# Bank_A-B-C-D.net
KiCad netlist of a schematic drawn in Altium Designer
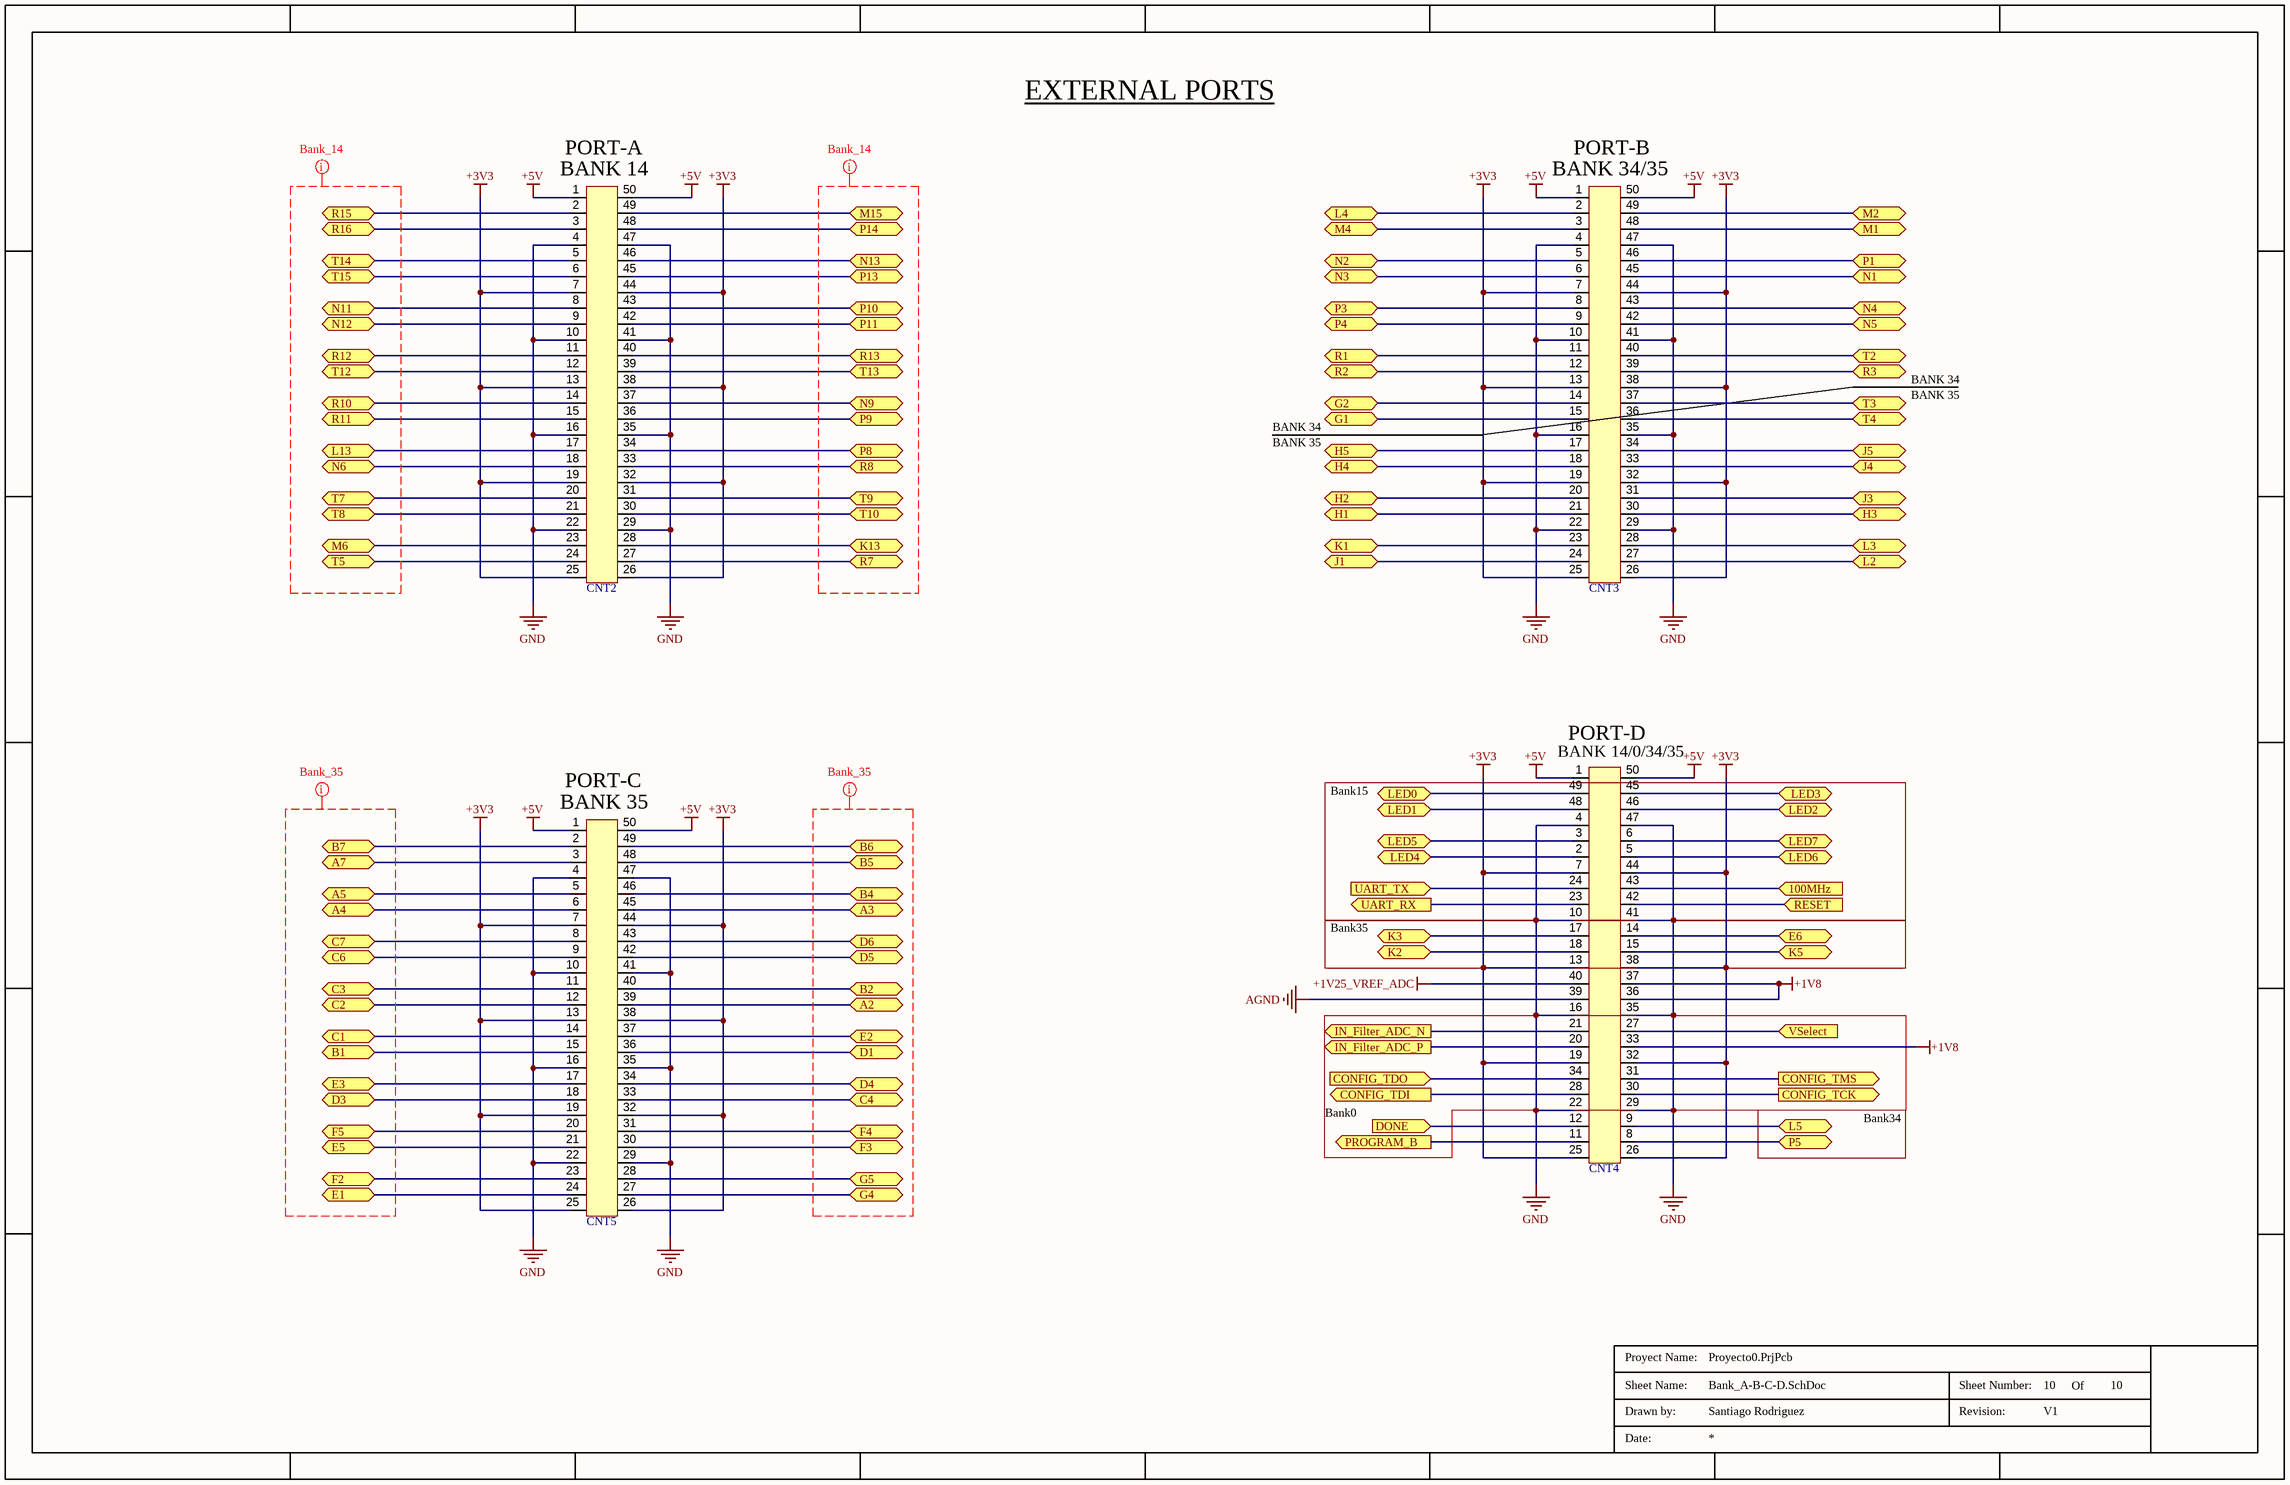
[diagram p0: Bank_A-B-C-D.SchDoc]

(export (version "E")
  (design (tool "Eeschema 10.0.6"))
  (components
    (comp (ref "CNT2")
      (value "528850574")
      (footprint "528850574")
      (description "CONN RCPT 50POS SMD GOLD")
      (fields (field (name "MANUFACTURER") "Molex") (field (name "PARTNUMBER") "0528850574"))
      (libsource (lib "Connectors") (part "528850574"))
    )
    (comp (ref "CNT3")
      (value "528850574")
      (footprint "528850574")
      (description "CONN RCPT 50POS SMD GOLD")
      (fields (field (name "MANUFACTURER") "Molex") (field (name "PARTNUMBER") "0528850574"))
      (libsource (lib "Connectors") (part "528850574"))
    )
    (comp (ref "CNT4")
      (value "528850574")
      (footprint "528850574")
      (description "CONN RCPT 50POS SMD GOLD")
      (fields (field (name "MANUFACTURER") "Molex") (field (name "PARTNUMBER") "0528850574"))
      (libsource (lib "") (part "528850574_1"))
    )
    (comp (ref "CNT5")
      (value "528850574")
      (footprint "528850574")
      (description "CONN RCPT 50POS SMD GOLD")
      (fields (field (name "MANUFACTURER") "Molex") (field (name "PARTNUMBER") "0528850574"))
      (libsource (lib "Connectors") (part "528850574"))
    )
  )
  (nets
    (net (code "1") (name "+1V8") (class "Default")
      (node (ref "CNT4") (pin "33") (pinfunction "33_33") (pintype "passive"))
      (node (ref "CNT4") (pin "36") (pinfunction "36_36") (pintype "passive"))
      (node (ref "CNT4") (pin "37") (pinfunction "37_37") (pintype "passive"))
    )
    (net (code "2") (name "+1V25_VREF_ADC") (class "Default")
      (node (ref "CNT4") (pin "40") (pinfunction "40_40") (pintype "passive"))
    )
    (net (code "3") (name "+3V3") (class "Default")
      (node (ref "CNT2") (pin "13") (pinfunction "13_13") (pintype "passive"))
      (node (ref "CNT2") (pin "19") (pinfunction "19_19") (pintype "passive"))
      (node (ref "CNT2") (pin "25") (pinfunction "25_25") (pintype "passive"))
      (node (ref "CNT2") (pin "26") (pinfunction "26_26") (pintype "passive"))
      (node (ref "CNT2") (pin "32") (pinfunction "32_32") (pintype "passive"))
      (node (ref "CNT2") (pin "38") (pinfunction "38_38") (pintype "passive"))
      (node (ref "CNT2") (pin "44") (pinfunction "44_44") (pintype "passive"))
      (node (ref "CNT2") (pin "7") (pinfunction "7_7") (pintype "passive"))
      (node (ref "CNT3") (pin "13") (pinfunction "13_13") (pintype "passive"))
      (node (ref "CNT3") (pin "19") (pinfunction "19_19") (pintype "passive"))
      (node (ref "CNT3") (pin "25") (pinfunction "25_25") (pintype "passive"))
      (node (ref "CNT3") (pin "26") (pinfunction "26_26") (pintype "passive"))
      (node (ref "CNT3") (pin "32") (pinfunction "32_32") (pintype "passive"))
      (node (ref "CNT3") (pin "38") (pinfunction "38_38") (pintype "passive"))
      (node (ref "CNT3") (pin "44") (pinfunction "44_44") (pintype "passive"))
      (node (ref "CNT3") (pin "7") (pinfunction "7_7") (pintype "passive"))
      (node (ref "CNT4") (pin "13") (pinfunction "13_13") (pintype "passive"))
      (node (ref "CNT4") (pin "19") (pinfunction "19_19") (pintype "passive"))
      (node (ref "CNT4") (pin "25") (pinfunction "25_25") (pintype "passive"))
      (node (ref "CNT4") (pin "26") (pinfunction "26_26") (pintype "passive"))
      (node (ref "CNT4") (pin "32") (pinfunction "32_32") (pintype "passive"))
      (node (ref "CNT4") (pin "38") (pinfunction "38_38") (pintype "passive"))
      (node (ref "CNT4") (pin "44") (pinfunction "44_44") (pintype "passive"))
      (node (ref "CNT4") (pin "7") (pinfunction "7_7") (pintype "passive"))
      (node (ref "CNT5") (pin "13") (pinfunction "13_13") (pintype "passive"))
      (node (ref "CNT5") (pin "19") (pinfunction "19_19") (pintype "passive"))
      (node (ref "CNT5") (pin "25") (pinfunction "25_25") (pintype "passive"))
      (node (ref "CNT5") (pin "26") (pinfunction "26_26") (pintype "passive"))
      (node (ref "CNT5") (pin "32") (pinfunction "32_32") (pintype "passive"))
      (node (ref "CNT5") (pin "38") (pinfunction "38_38") (pintype "passive"))
      (node (ref "CNT5") (pin "44") (pinfunction "44_44") (pintype "passive"))
      (node (ref "CNT5") (pin "7") (pinfunction "7_7") (pintype "passive"))
    )
    (net (code "4") (name "+5V") (class "Default")
      (node (ref "CNT2") (pin "1") (pintype "passive"))
      (node (ref "CNT2") (pin "50") (pinfunction "50_50") (pintype "passive"))
      (node (ref "CNT3") (pin "1") (pintype "passive"))
      (node (ref "CNT3") (pin "50") (pinfunction "50_50") (pintype "passive"))
      (node (ref "CNT4") (pin "1") (pintype "passive"))
      (node (ref "CNT4") (pin "50") (pinfunction "50_50") (pintype "passive"))
      (node (ref "CNT5") (pin "1") (pintype "passive"))
      (node (ref "CNT5") (pin "50") (pinfunction "50_50") (pintype "passive"))
    )
    (net (code "5") (name "/100MHz") (class "Default")
      (node (ref "CNT4") (pin "43") (pinfunction "43_43") (pintype "passive"))
    )
    (net (code "6") (name "/A2") (class "Default")
      (node (ref "CNT5") (pin "39") (pinfunction "39_39") (pintype "passive"))
    )
    (net (code "7") (name "/A3") (class "Default")
      (node (ref "CNT5") (pin "45") (pinfunction "45_45") (pintype "passive"))
    )
    (net (code "8") (name "/A4") (class "Default")
      (node (ref "CNT5") (pin "6") (pinfunction "6_6") (pintype "passive"))
    )
    (net (code "9") (name "/A5") (class "Default")
      (node (ref "CNT5") (pin "5") (pinfunction "5_5") (pintype "passive"))
    )
    (net (code "10") (name "/A7") (class "Default") (node (ref "CNT5") (pin "3") (pintype "passive")))
    (net (code "11") (name "/B1") (class "Default")
      (node (ref "CNT5") (pin "15") (pinfunction "15_15") (pintype "passive"))
    )
    (net (code "12") (name "/B2") (class "Default")
      (node (ref "CNT5") (pin "40") (pinfunction "40_40") (pintype "passive"))
    )
    (net (code "13") (name "/B4") (class "Default")
      (node (ref "CNT5") (pin "46") (pinfunction "46_46") (pintype "passive"))
    )
    (net (code "14") (name "/B5") (class "Default")
      (node (ref "CNT5") (pin "48") (pinfunction "48_48") (pintype "passive"))
    )
    (net (code "15") (name "/B6") (class "Default")
      (node (ref "CNT5") (pin "49") (pinfunction "49_49") (pintype "passive"))
    )
    (net (code "16") (name "/B7") (class "Default") (node (ref "CNT5") (pin "2") (pintype "passive")))
    (net (code "17") (name "/C1") (class "Default")
      (node (ref "CNT5") (pin "14") (pinfunction "14_14") (pintype "passive"))
    )
    (net (code "18") (name "/C2") (class "Default")
      (node (ref "CNT5") (pin "12") (pinfunction "12_12") (pintype "passive"))
    )
    (net (code "19") (name "/C3") (class "Default")
      (node (ref "CNT5") (pin "11") (pinfunction "11_11") (pintype "passive"))
    )
    (net (code "20") (name "/C4") (class "Default")
      (node (ref "CNT5") (pin "33") (pinfunction "33_33") (pintype "passive"))
    )
    (net (code "21") (name "/C6") (class "Default")
      (node (ref "CNT5") (pin "9") (pinfunction "9_9") (pintype "passive"))
    )
    (net (code "22") (name "/C7") (class "Default")
      (node (ref "CNT5") (pin "8") (pinfunction "8_8") (pintype "passive"))
    )
    (net (code "23") (name "/CONFIG_TCK") (class "Default")
      (node (ref "CNT4") (pin "30") (pinfunction "30_30") (pintype "passive"))
    )
    (net (code "24") (name "/CONFIG_TDI") (class "Default")
      (node (ref "CNT4") (pin "28") (pinfunction "28_28") (pintype "passive"))
    )
    (net (code "25") (name "/CONFIG_TDO") (class "Default")
      (node (ref "CNT4") (pin "34") (pinfunction "34_34") (pintype "passive"))
    )
    (net (code "26") (name "/CONFIG_TMS") (class "Default")
      (node (ref "CNT4") (pin "31") (pinfunction "31_31") (pintype "passive"))
    )
    (net (code "27") (name "/D1") (class "Default")
      (node (ref "CNT5") (pin "36") (pinfunction "36_36") (pintype "passive"))
    )
    (net (code "28") (name "/D3") (class "Default")
      (node (ref "CNT5") (pin "18") (pinfunction "18_18") (pintype "passive"))
    )
    (net (code "29") (name "/D4") (class "Default")
      (node (ref "CNT5") (pin "34") (pinfunction "34_34") (pintype "passive"))
    )
    (net (code "30") (name "/D5") (class "Default")
      (node (ref "CNT5") (pin "42") (pinfunction "42_42") (pintype "passive"))
    )
    (net (code "31") (name "/D6") (class "Default")
      (node (ref "CNT5") (pin "43") (pinfunction "43_43") (pintype "passive"))
    )
    (net (code "32") (name "/DONE") (class "Default")
      (node (ref "CNT4") (pin "12") (pinfunction "12_12") (pintype "passive"))
    )
    (net (code "33") (name "/E1") (class "Default")
      (node (ref "CNT5") (pin "24") (pinfunction "24_24") (pintype "passive"))
    )
    (net (code "34") (name "/E2") (class "Default")
      (node (ref "CNT5") (pin "37") (pinfunction "37_37") (pintype "passive"))
    )
    (net (code "35") (name "/E3") (class "Default")
      (node (ref "CNT5") (pin "17") (pinfunction "17_17") (pintype "passive"))
    )
    (net (code "36") (name "/E5") (class "Default")
      (node (ref "CNT5") (pin "21") (pinfunction "21_21") (pintype "passive"))
    )
    (net (code "37") (name "/E6") (class "Default")
      (node (ref "CNT4") (pin "14") (pinfunction "14_14") (pintype "passive"))
    )
    (net (code "38") (name "/F2") (class "Default")
      (node (ref "CNT5") (pin "23") (pinfunction "23_23") (pintype "passive"))
    )
    (net (code "39") (name "/F3") (class "Default")
      (node (ref "CNT5") (pin "30") (pinfunction "30_30") (pintype "passive"))
    )
    (net (code "40") (name "/F4") (class "Default")
      (node (ref "CNT5") (pin "31") (pinfunction "31_31") (pintype "passive"))
    )
    (net (code "41") (name "/F5") (class "Default")
      (node (ref "CNT5") (pin "20") (pinfunction "20_20") (pintype "passive"))
    )
    (net (code "42") (name "/G1") (class "Default")
      (node (ref "CNT3") (pin "15") (pinfunction "15_15") (pintype "passive"))
    )
    (net (code "43") (name "/G2") (class "Default")
      (node (ref "CNT3") (pin "14") (pinfunction "14_14") (pintype "passive"))
    )
    (net (code "44") (name "/G4") (class "Default")
      (node (ref "CNT5") (pin "27") (pinfunction "27_27") (pintype "passive"))
    )
    (net (code "45") (name "/G5") (class "Default")
      (node (ref "CNT5") (pin "28") (pinfunction "28_28") (pintype "passive"))
    )
    (net (code "46") (name "/H1") (class "Default")
      (node (ref "CNT3") (pin "21") (pinfunction "21_21") (pintype "passive"))
    )
    (net (code "47") (name "/H2") (class "Default")
      (node (ref "CNT3") (pin "20") (pinfunction "20_20") (pintype "passive"))
    )
    (net (code "48") (name "/H3") (class "Default")
      (node (ref "CNT3") (pin "30") (pinfunction "30_30") (pintype "passive"))
    )
    (net (code "49") (name "/H4") (class "Default")
      (node (ref "CNT3") (pin "18") (pinfunction "18_18") (pintype "passive"))
    )
    (net (code "50") (name "/H5") (class "Default")
      (node (ref "CNT3") (pin "17") (pinfunction "17_17") (pintype "passive"))
    )
    (net (code "51") (name "/IN_Filter_ADC_N") (class "Default")
      (node (ref "CNT4") (pin "21") (pinfunction "21_21") (pintype "passive"))
    )
    (net (code "52") (name "/IN_Filter_ADC_P") (class "Default")
      (node (ref "CNT4") (pin "20") (pinfunction "20_20") (pintype "passive"))
    )
    (net (code "53") (name "/J1") (class "Default")
      (node (ref "CNT3") (pin "24") (pinfunction "24_24") (pintype "passive"))
    )
    (net (code "54") (name "/J3") (class "Default")
      (node (ref "CNT3") (pin "31") (pinfunction "31_31") (pintype "passive"))
    )
    (net (code "55") (name "/J4") (class "Default")
      (node (ref "CNT3") (pin "33") (pinfunction "33_33") (pintype "passive"))
    )
    (net (code "56") (name "/J5") (class "Default")
      (node (ref "CNT3") (pin "34") (pinfunction "34_34") (pintype "passive"))
    )
    (net (code "57") (name "/K1") (class "Default")
      (node (ref "CNT3") (pin "23") (pinfunction "23_23") (pintype "passive"))
    )
    (net (code "58") (name "/K2") (class "Default")
      (node (ref "CNT4") (pin "18") (pinfunction "18_18") (pintype "passive"))
    )
    (net (code "59") (name "/K3") (class "Default")
      (node (ref "CNT4") (pin "17") (pinfunction "17_17") (pintype "passive"))
    )
    (net (code "60") (name "/K5") (class "Default")
      (node (ref "CNT4") (pin "15") (pinfunction "15_15") (pintype "passive"))
    )
    (net (code "61") (name "/K13") (class "Default")
      (node (ref "CNT2") (pin "28") (pinfunction "28_28") (pintype "passive"))
    )
    (net (code "62") (name "/L2") (class "Default")
      (node (ref "CNT3") (pin "27") (pinfunction "27_27") (pintype "passive"))
    )
    (net (code "63") (name "/L3") (class "Default")
      (node (ref "CNT3") (pin "28") (pinfunction "28_28") (pintype "passive"))
    )
    (net (code "64") (name "/L4") (class "Default") (node (ref "CNT3") (pin "2") (pintype "passive")))
    (net (code "65") (name "/L5") (class "Default")
      (node (ref "CNT4") (pin "9") (pinfunction "9_9") (pintype "passive"))
    )
    (net (code "66") (name "/L13") (class "Default")
      (node (ref "CNT2") (pin "17") (pinfunction "17_17") (pintype "passive"))
    )
    (net (code "67") (name "/LED0") (class "Default")
      (node (ref "CNT4") (pin "49") (pinfunction "49_49") (pintype "passive"))
    )
    (net (code "68") (name "/LED1") (class "Default")
      (node (ref "CNT4") (pin "48") (pinfunction "48_48") (pintype "passive"))
    )
    (net (code "69") (name "/LED2") (class "Default")
      (node (ref "CNT4") (pin "46") (pinfunction "46_46") (pintype "passive"))
    )
    (net (code "70") (name "/LED3") (class "Default")
      (node (ref "CNT4") (pin "45") (pinfunction "45_45") (pintype "passive"))
    )
    (net (code "71") (name "/LED4") (class "Default") (node (ref "CNT4") (pin "2") (pintype "passive")))
    (net (code "72") (name "/LED5") (class "Default") (node (ref "CNT4") (pin "3") (pintype "passive")))
    (net (code "73") (name "/LED6") (class "Default")
      (node (ref "CNT4") (pin "5") (pinfunction "5_5") (pintype "passive"))
    )
    (net (code "74") (name "/LED7") (class "Default")
      (node (ref "CNT4") (pin "6") (pinfunction "6_6") (pintype "passive"))
    )
    (net (code "75") (name "/M1") (class "Default")
      (node (ref "CNT3") (pin "48") (pinfunction "48_48") (pintype "passive"))
    )
    (net (code "76") (name "/M2") (class "Default")
      (node (ref "CNT3") (pin "49") (pinfunction "49_49") (pintype "passive"))
    )
    (net (code "77") (name "/M4") (class "Default") (node (ref "CNT3") (pin "3") (pintype "passive")))
    (net (code "78") (name "/M6") (class "Default")
      (node (ref "CNT2") (pin "23") (pinfunction "23_23") (pintype "passive"))
    )
    (net (code "79") (name "/M15") (class "Default")
      (node (ref "CNT2") (pin "49") (pinfunction "49_49") (pintype "passive"))
    )
    (net (code "80") (name "/N1") (class "Default")
      (node (ref "CNT3") (pin "45") (pinfunction "45_45") (pintype "passive"))
    )
    (net (code "81") (name "/N2") (class "Default")
      (node (ref "CNT3") (pin "5") (pinfunction "5_5") (pintype "passive"))
    )
    (net (code "82") (name "/N3") (class "Default")
      (node (ref "CNT3") (pin "6") (pinfunction "6_6") (pintype "passive"))
    )
    (net (code "83") (name "/N4") (class "Default")
      (node (ref "CNT3") (pin "43") (pinfunction "43_43") (pintype "passive"))
    )
    (net (code "84") (name "/N5") (class "Default")
      (node (ref "CNT3") (pin "42") (pinfunction "42_42") (pintype "passive"))
    )
    (net (code "85") (name "/N6") (class "Default")
      (node (ref "CNT2") (pin "18") (pinfunction "18_18") (pintype "passive"))
    )
    (net (code "86") (name "/N9") (class "Default")
      (node (ref "CNT2") (pin "37") (pinfunction "37_37") (pintype "passive"))
    )
    (net (code "87") (name "/N11") (class "Default")
      (node (ref "CNT2") (pin "8") (pinfunction "8_8") (pintype "passive"))
    )
    (net (code "88") (name "/N12") (class "Default")
      (node (ref "CNT2") (pin "9") (pinfunction "9_9") (pintype "passive"))
    )
    (net (code "89") (name "/N13") (class "Default")
      (node (ref "CNT2") (pin "46") (pinfunction "46_46") (pintype "passive"))
    )
    (net (code "90") (name "/P1") (class "Default")
      (node (ref "CNT3") (pin "46") (pinfunction "46_46") (pintype "passive"))
    )
    (net (code "91") (name "/P3") (class "Default")
      (node (ref "CNT3") (pin "8") (pinfunction "8_8") (pintype "passive"))
    )
    (net (code "92") (name "/P4") (class "Default")
      (node (ref "CNT3") (pin "9") (pinfunction "9_9") (pintype "passive"))
    )
    (net (code "93") (name "/P5") (class "Default")
      (node (ref "CNT4") (pin "8") (pinfunction "8_8") (pintype "passive"))
    )
    (net (code "94") (name "/P8") (class "Default")
      (node (ref "CNT2") (pin "34") (pinfunction "34_34") (pintype "passive"))
    )
    (net (code "95") (name "/P9") (class "Default")
      (node (ref "CNT2") (pin "36") (pinfunction "36_36") (pintype "passive"))
    )
    (net (code "96") (name "/P10") (class "Default")
      (node (ref "CNT2") (pin "43") (pinfunction "43_43") (pintype "passive"))
    )
    (net (code "97") (name "/P11") (class "Default")
      (node (ref "CNT2") (pin "42") (pinfunction "42_42") (pintype "passive"))
    )
    (net (code "98") (name "/P13") (class "Default")
      (node (ref "CNT2") (pin "45") (pinfunction "45_45") (pintype "passive"))
    )
    (net (code "99") (name "/P14") (class "Default")
      (node (ref "CNT2") (pin "48") (pinfunction "48_48") (pintype "passive"))
    )
    (net (code "100") (name "/PROGRAM_B") (class "Default")
      (node (ref "CNT4") (pin "11") (pinfunction "11_11") (pintype "passive"))
    )
    (net (code "101") (name "/R1") (class "Default")
      (node (ref "CNT3") (pin "11") (pinfunction "11_11") (pintype "passive"))
    )
    (net (code "102") (name "/R2") (class "Default")
      (node (ref "CNT3") (pin "12") (pinfunction "12_12") (pintype "passive"))
    )
    (net (code "103") (name "/R3") (class "Default")
      (node (ref "CNT3") (pin "39") (pinfunction "39_39") (pintype "passive"))
    )
    (net (code "104") (name "/R7") (class "Default")
      (node (ref "CNT2") (pin "27") (pinfunction "27_27") (pintype "passive"))
    )
    (net (code "105") (name "/R8") (class "Default")
      (node (ref "CNT2") (pin "33") (pinfunction "33_33") (pintype "passive"))
    )
    (net (code "106") (name "/R10") (class "Default")
      (node (ref "CNT2") (pin "14") (pinfunction "14_14") (pintype "passive"))
    )
    (net (code "107") (name "/R11") (class "Default")
      (node (ref "CNT2") (pin "15") (pinfunction "15_15") (pintype "passive"))
    )
    (net (code "108") (name "/R12") (class "Default")
      (node (ref "CNT2") (pin "11") (pinfunction "11_11") (pintype "passive"))
    )
    (net (code "109") (name "/R13") (class "Default")
      (node (ref "CNT2") (pin "40") (pinfunction "40_40") (pintype "passive"))
    )
    (net (code "110") (name "/R15") (class "Default") (node (ref "CNT2") (pin "2") (pintype "passive")))
    (net (code "111") (name "/R16") (class "Default") (node (ref "CNT2") (pin "3") (pintype "passive")))
    (net (code "112") (name "/RESET") (class "Default")
      (node (ref "CNT4") (pin "42") (pinfunction "42_42") (pintype "passive"))
    )
    (net (code "113") (name "/T2") (class "Default")
      (node (ref "CNT3") (pin "40") (pinfunction "40_40") (pintype "passive"))
    )
    (net (code "114") (name "/T3") (class "Default")
      (node (ref "CNT3") (pin "37") (pinfunction "37_37") (pintype "passive"))
    )
    (net (code "115") (name "/T4") (class "Default")
      (node (ref "CNT3") (pin "36") (pinfunction "36_36") (pintype "passive"))
    )
    (net (code "116") (name "/T5") (class "Default")
      (node (ref "CNT2") (pin "24") (pinfunction "24_24") (pintype "passive"))
    )
    (net (code "117") (name "/T7") (class "Default")
      (node (ref "CNT2") (pin "20") (pinfunction "20_20") (pintype "passive"))
    )
    (net (code "118") (name "/T8") (class "Default")
      (node (ref "CNT2") (pin "21") (pinfunction "21_21") (pintype "passive"))
    )
    (net (code "119") (name "/T9") (class "Default")
      (node (ref "CNT2") (pin "31") (pinfunction "31_31") (pintype "passive"))
    )
    (net (code "120") (name "/T10") (class "Default")
      (node (ref "CNT2") (pin "30") (pinfunction "30_30") (pintype "passive"))
    )
    (net (code "121") (name "/T12") (class "Default")
      (node (ref "CNT2") (pin "12") (pinfunction "12_12") (pintype "passive"))
    )
    (net (code "122") (name "/T13") (class "Default")
      (node (ref "CNT2") (pin "39") (pinfunction "39_39") (pintype "passive"))
    )
    (net (code "123") (name "/T14") (class "Default")
      (node (ref "CNT2") (pin "5") (pinfunction "5_5") (pintype "passive"))
    )
    (net (code "124") (name "/T15") (class "Default")
      (node (ref "CNT2") (pin "6") (pinfunction "6_6") (pintype "passive"))
    )
    (net (code "125") (name "/UART_RX") (class "Default")
      (node (ref "CNT4") (pin "23") (pinfunction "23_23") (pintype "passive"))
    )
    (net (code "126") (name "/UART_TX") (class "Default")
      (node (ref "CNT4") (pin "24") (pinfunction "24_24") (pintype "passive"))
    )
    (net (code "127") (name "/VSelect") (class "Default")
      (node (ref "CNT4") (pin "27") (pinfunction "27_27") (pintype "passive"))
    )
    (net (code "128") (name "AGND") (class "Default")
      (node (ref "CNT4") (pin "39") (pinfunction "39_39") (pintype "passive"))
    )
    (net (code "129") (name "GND") (class "Default")
      (node (ref "CNT2") (pin "10") (pinfunction "10_10") (pintype "passive"))
      (node (ref "CNT2") (pin "16") (pinfunction "16_16") (pintype "passive"))
      (node (ref "CNT2") (pin "22") (pinfunction "22_22") (pintype "passive"))
      (node (ref "CNT2") (pin "29") (pinfunction "29_29") (pintype "passive"))
      (node (ref "CNT2") (pin "35") (pinfunction "35_35") (pintype "passive"))
      (node (ref "CNT2") (pin "4") (pinfunction "4_4") (pintype "passive"))
      (node (ref "CNT2") (pin "41") (pinfunction "41_41") (pintype "passive"))
      (node (ref "CNT2") (pin "47") (pinfunction "47_47") (pintype "passive"))
      (node (ref "CNT3") (pin "10") (pinfunction "10_10") (pintype "passive"))
      (node (ref "CNT3") (pin "16") (pinfunction "16_16") (pintype "passive"))
      (node (ref "CNT3") (pin "22") (pinfunction "22_22") (pintype "passive"))
      (node (ref "CNT3") (pin "29") (pinfunction "29_29") (pintype "passive"))
      (node (ref "CNT3") (pin "35") (pinfunction "35_35") (pintype "passive"))
      (node (ref "CNT3") (pin "4") (pinfunction "4_4") (pintype "passive"))
      (node (ref "CNT3") (pin "41") (pinfunction "41_41") (pintype "passive"))
      (node (ref "CNT3") (pin "47") (pinfunction "47_47") (pintype "passive"))
      (node (ref "CNT4") (pin "10") (pinfunction "10_10") (pintype "passive"))
      (node (ref "CNT4") (pin "16") (pinfunction "16_16") (pintype "passive"))
      (node (ref "CNT4") (pin "22") (pinfunction "22_22") (pintype "passive"))
      (node (ref "CNT4") (pin "29") (pinfunction "29_29") (pintype "passive"))
      (node (ref "CNT4") (pin "35") (pinfunction "35_35") (pintype "passive"))
      (node (ref "CNT4") (pin "4") (pinfunction "4_4") (pintype "passive"))
      (node (ref "CNT4") (pin "41") (pinfunction "41_41") (pintype "passive"))
      (node (ref "CNT4") (pin "47") (pinfunction "47_47") (pintype "passive"))
      (node (ref "CNT5") (pin "10") (pinfunction "10_10") (pintype "passive"))
      (node (ref "CNT5") (pin "16") (pinfunction "16_16") (pintype "passive"))
      (node (ref "CNT5") (pin "22") (pinfunction "22_22") (pintype "passive"))
      (node (ref "CNT5") (pin "29") (pinfunction "29_29") (pintype "passive"))
      (node (ref "CNT5") (pin "35") (pinfunction "35_35") (pintype "passive"))
      (node (ref "CNT5") (pin "4") (pinfunction "4_4") (pintype "passive"))
      (node (ref "CNT5") (pin "41") (pinfunction "41_41") (pintype "passive"))
      (node (ref "CNT5") (pin "47") (pinfunction "47_47") (pintype "passive"))
    )
  )
)
